# Wolf.net
KiCad netlist of a schematic drawn in EAGLE
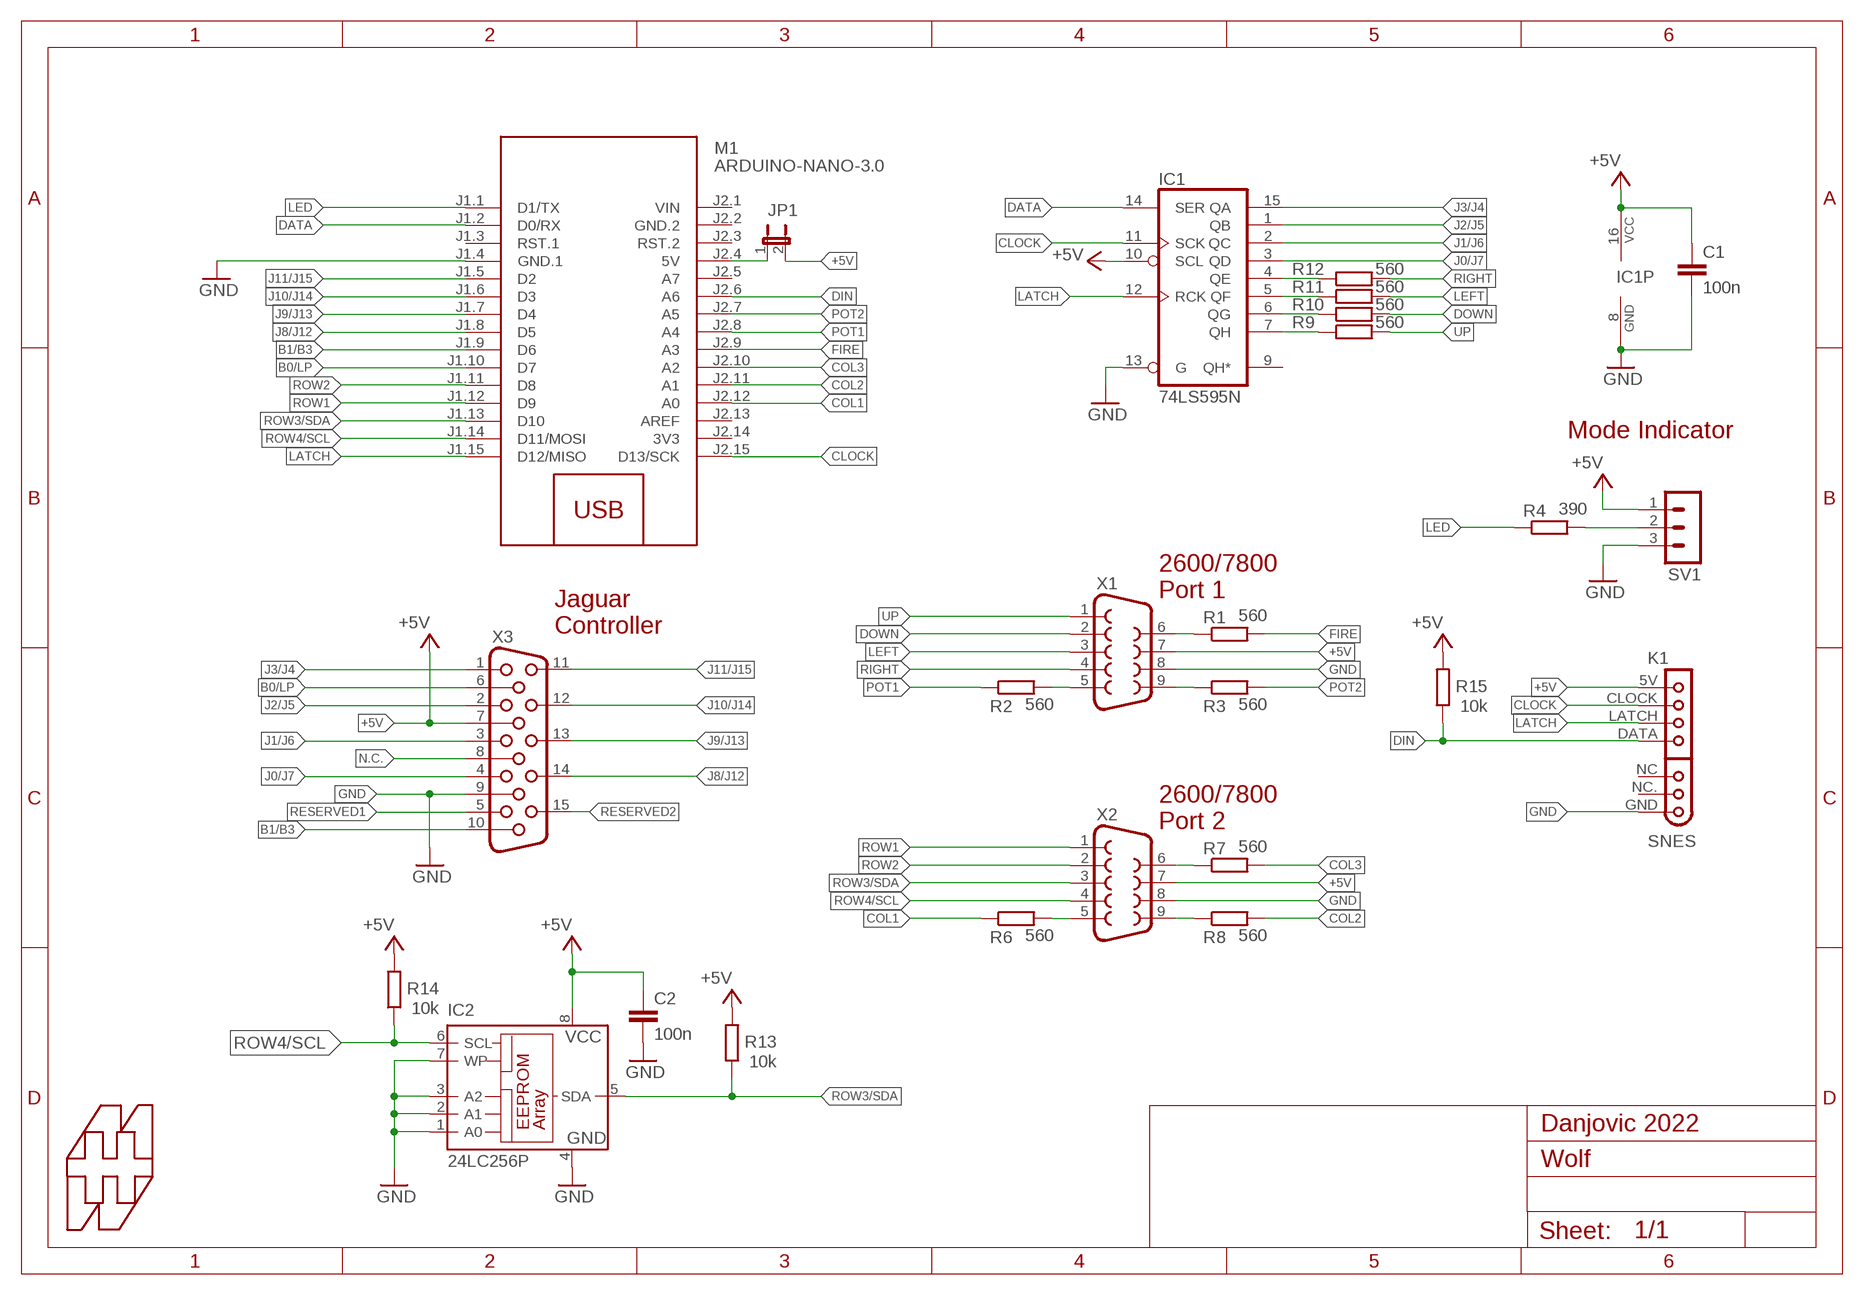
[diagram p0: schematic, sheet 1]

(export (version "E")
  (design (tool "Eeschema 10.0.6"))
  (components
    (comp (ref "C1")
      (value "100n")
      (footprint "eagle-import:C050-024X044")
      (libsource (lib "eagle-import") (part "C-EU050-024X044"))
    )
    (comp (ref "C2")
      (value "100n")
      (footprint "eagle-import:C050-024X044")
      (libsource (lib "eagle-import") (part "C-EU050-024X044"))
    )
    (comp (ref "IC1")
      (value "74LS595N")
      (footprint "eagle-import:DIL16")
      (libsource (lib "eagle-import") (part "74595NLS"))
    )
    (comp (ref "IC2")
      (value "24LC256P")
      (footprint "eagle-import:DIL8")
      (fields (field (name "MF") "MICROCHIP") (field (name "MPN") "24LC256-E/P"))
      (libsource (lib "eagle-import") (part "24PLC256"))
    )
    (comp (ref "JP1")
      (value "JP1E")
      (footprint "eagle-import:JP1")
      (libsource (lib "eagle-import") (part "JP1E"))
    )
    (comp (ref "K1")
      (value "SNES")
      (footprint "eagle-import:SNESCON-R")
      (libsource (lib "eagle-import") (part "SNES-R"))
    )
    (comp (ref "M1")
      (value "ARDUINO-NANO-3.0")
      (footprint "eagle-import:ARDUINO-NANO-3.0")
      (libsource (lib "eagle-import") (part "ARDUINO-NANO-3.0"))
    )
    (comp (ref "R1")
      (value "560")
      (footprint "eagle-import:0204_7")
      (libsource (lib "eagle-import") (part "R-EU_0204/7"))
    )
    (comp (ref "R2")
      (value "560")
      (footprint "eagle-import:0204_7")
      (libsource (lib "eagle-import") (part "R-EU_0204/7"))
    )
    (comp (ref "R3")
      (value "560")
      (footprint "eagle-import:0204_7")
      (libsource (lib "eagle-import") (part "R-EU_0204/7"))
    )
    (comp (ref "R4")
      (value "390")
      (footprint "eagle-import:0204_7")
      (libsource (lib "eagle-import") (part "R-EU_0204/7"))
    )
    (comp (ref "R6")
      (value "560")
      (footprint "eagle-import:0204_7")
      (libsource (lib "eagle-import") (part "R-EU_0204/7"))
    )
    (comp (ref "R7")
      (value "560")
      (footprint "eagle-import:0204_7")
      (libsource (lib "eagle-import") (part "R-EU_0204/7"))
    )
    (comp (ref "R8")
      (value "560")
      (footprint "eagle-import:0204_7")
      (libsource (lib "eagle-import") (part "R-EU_0204/7"))
    )
    (comp (ref "R9")
      (value "560")
      (footprint "eagle-import:0204_7")
      (libsource (lib "eagle-import") (part "R-EU_0204/7"))
    )
    (comp (ref "R10")
      (value "560")
      (footprint "eagle-import:0204_7")
      (libsource (lib "eagle-import") (part "R-EU_0204/7"))
    )
    (comp (ref "R11")
      (value "560")
      (footprint "eagle-import:0204_7")
      (libsource (lib "eagle-import") (part "R-EU_0204/7"))
    )
    (comp (ref "R12")
      (value "560")
      (footprint "eagle-import:0204_7")
      (libsource (lib "eagle-import") (part "R-EU_0204/7"))
    )
    (comp (ref "R13")
      (value "10k")
      (footprint "eagle-import:0204_7")
      (libsource (lib "eagle-import") (part "R-EU_0204/7"))
    )
    (comp (ref "R14")
      (value "10k")
      (footprint "eagle-import:0204_7")
      (libsource (lib "eagle-import") (part "R-EU_0204/7"))
    )
    (comp (ref "R15")
      (value "10k")
      (footprint "eagle-import:0204_7")
      (libsource (lib "eagle-import") (part "R-EU_0204/7"))
    )
    (comp (ref "SV1")
      (value "MA03-1")
      (footprint "eagle-import:MA03-1")
      (libsource (lib "eagle-import") (part "MA03-1"))
    )
    (comp (ref "U$1")
      (value "HAMMOND-RL6015")
      (footprint "eagle-import:RL6015")
      (libsource (lib "eagle-import") (part "HAMMOND-RL6015"))
    )
    (comp (ref "X1")
      (value "F09HP")
      (footprint "eagle-import:F09HP")
      (libsource (lib "eagle-import") (part "F09HP"))
    )
    (comp (ref "X2")
      (value "F09HP")
      (footprint "eagle-import:F09HP")
      (libsource (lib "eagle-import") (part "F09HP"))
    )
    (comp (ref "X3")
      (value "HF15H")
      (footprint "eagle-import:HDF15H")
      (libsource (lib "eagle-import") (part "HF15H"))
    )
  )
  (nets
    (net (code "1") (name "+5V") (class "Default")
      (node (ref "C1") (pin "1") (pinfunction "1_1") (pintype "passive"))
      (node (ref "C2") (pin "1") (pinfunction "1_1") (pintype "passive"))
      (node (ref "IC1") (pin "10") (pinfunction "SCL_10") (pintype "input"))
      (node (ref "IC1") (pin "16") (pinfunction "VCC_16") (pintype "power_in"))
      (node (ref "IC2") (pin "8") (pinfunction "VCC_8") (pintype "power_in"))
      (node (ref "JP1") (pin "2") (pinfunction "2_2") (pintype "passive"))
      (node (ref "K1") (pin "5V") (pinfunction "1_5V") (pintype "passive"))
      (node (ref "R13") (pin "2") (pinfunction "2_2") (pintype "passive"))
      (node (ref "R14") (pin "2") (pinfunction "2_2") (pintype "passive"))
      (node (ref "R15") (pin "2") (pinfunction "2_2") (pintype "passive"))
      (node (ref "SV1") (pin "1") (pinfunction "1_1") (pintype "passive"))
      (node (ref "X1") (pin "7") (pinfunction "7_7") (pintype "passive"))
      (node (ref "X2") (pin "7") (pinfunction "7_7") (pintype "passive"))
      (node (ref "X3") (pin "7") (pinfunction "7_7") (pintype "passive"))
    )
    (net (code "2") (name "/3V3") (class "Default")
      (node (ref "M1") (pin "J2.14") (pinfunction "3V3_J2.14") (pintype "power_in"))
    )
    (net (code "3") (name "/GND.2") (class "Default")
      (node (ref "M1") (pin "J2.2") (pinfunction "GND.2_J2.2") (pintype "power_in"))
    )
    (net (code "4") (name "/VIN") (class "Default")
      (node (ref "M1") (pin "J2.1") (pinfunction "VIN_J2.1") (pintype "power_in"))
    )
    (net (code "5") (name "B0{slash}LP") (class "Default")
      (node (ref "M1") (pin "J1.10") (pinfunction "D7_J1.10") (pintype "bidirectional"))
      (node (ref "X3") (pin "6") (pinfunction "6_6") (pintype "passive"))
    )
    (net (code "6") (name "B1{slash}B3") (class "Default")
      (node (ref "M1") (pin "J1.9") (pinfunction "D6_J1.9") (pintype "bidirectional"))
      (node (ref "X3") (pin "10") (pinfunction "10_10") (pintype "passive"))
    )
    (net (code "7") (name "CLOCK") (class "Default")
      (node (ref "IC1") (pin "11") (pinfunction "SCK_11") (pintype "input"))
      (node (ref "K1") (pin "CLOCK") (pinfunction "2_CLOCK") (pintype "passive"))
      (node (ref "M1") (pin "J2.15") (pinfunction "D13/SCK_J2.15") (pintype "bidirectional"))
    )
    (net (code "8") (name "COL1") (class "Default")
      (node (ref "M1") (pin "J2.12") (pinfunction "A0_J2.12") (pintype "bidirectional"))
      (node (ref "R6") (pin "1") (pinfunction "1_1") (pintype "passive"))
    )
    (net (code "9") (name "COL2") (class "Default")
      (node (ref "M1") (pin "J2.11") (pinfunction "A1_J2.11") (pintype "bidirectional"))
      (node (ref "R8") (pin "2") (pinfunction "2_2") (pintype "passive"))
    )
    (net (code "10") (name "COL3") (class "Default")
      (node (ref "M1") (pin "J2.10") (pinfunction "A2_J2.10") (pintype "bidirectional"))
      (node (ref "R7") (pin "2") (pinfunction "2_2") (pintype "passive"))
    )
    (net (code "11") (name "DATA") (class "Default")
      (node (ref "IC1") (pin "14") (pinfunction "SER_14") (pintype "input"))
      (node (ref "M1") (pin "J1.2") (pinfunction "D0/RX_J1.2") (pintype "bidirectional"))
    )
    (net (code "12") (name "DIN") (class "Default")
      (node (ref "K1") (pin "DATA") (pinfunction "4_DATA") (pintype "passive"))
      (node (ref "M1") (pin "J2.6") (pinfunction "A6_J2.6") (pintype "bidirectional"))
      (node (ref "R15") (pin "1") (pinfunction "1_1") (pintype "passive"))
    )
    (net (code "13") (name "DOWN") (class "Default")
      (node (ref "R10") (pin "2") (pinfunction "2_2") (pintype "passive"))
      (node (ref "X1") (pin "2") (pinfunction "2_2") (pintype "passive"))
    )
    (net (code "14") (name "FIRE") (class "Default")
      (node (ref "M1") (pin "J2.9") (pinfunction "A3_J2.9") (pintype "bidirectional"))
      (node (ref "R1") (pin "2") (pinfunction "2_2") (pintype "passive"))
    )
    (net (code "15") (name "GND") (class "Default")
      (node (ref "C1") (pin "2") (pinfunction "2_2") (pintype "passive"))
      (node (ref "C2") (pin "2") (pinfunction "2_2") (pintype "passive"))
      (node (ref "IC1") (pin "13") (pinfunction "G_13") (pintype "input"))
      (node (ref "IC1") (pin "8") (pinfunction "GND_8") (pintype "power_in"))
      (node (ref "IC2") (pin "1") (pinfunction "A0_1") (pintype "input"))
      (node (ref "IC2") (pin "2") (pinfunction "A1_2") (pintype "input"))
      (node (ref "IC2") (pin "3") (pinfunction "A2_3") (pintype "input"))
      (node (ref "IC2") (pin "4") (pinfunction "GND_4") (pintype "power_in"))
      (node (ref "IC2") (pin "7") (pinfunction "WP_7") (pintype "input"))
      (node (ref "K1") (pin "GND") (pinfunction "7_GND") (pintype "passive"))
      (node (ref "M1") (pin "J1.4") (pinfunction "GND.1_J1.4") (pintype "power_in"))
      (node (ref "SV1") (pin "3") (pinfunction "3_3") (pintype "passive"))
      (node (ref "X1") (pin "8") (pinfunction "8_8") (pintype "passive"))
      (node (ref "X2") (pin "8") (pinfunction "8_8") (pintype "passive"))
      (node (ref "X3") (pin "9") (pinfunction "9_9") (pintype "passive"))
    )
    (net (code "16") (name "J0{slash}J7") (class "Default")
      (node (ref "IC1") (pin "3") (pinfunction "QD_3") (pintype "tri_state"))
      (node (ref "X3") (pin "4") (pinfunction "4_4") (pintype "passive"))
    )
    (net (code "17") (name "J1{slash}J6") (class "Default")
      (node (ref "IC1") (pin "2") (pinfunction "QC_2") (pintype "tri_state"))
      (node (ref "X3") (pin "3") (pinfunction "3_3") (pintype "passive"))
    )
    (net (code "18") (name "J2{slash}J5") (class "Default")
      (node (ref "IC1") (pin "1") (pinfunction "QB_1") (pintype "tri_state"))
      (node (ref "X3") (pin "2") (pinfunction "2_2") (pintype "passive"))
    )
    (net (code "19") (name "J3{slash}J4") (class "Default")
      (node (ref "IC1") (pin "15") (pinfunction "QA_15") (pintype "tri_state"))
      (node (ref "X3") (pin "1") (pinfunction "1_1") (pintype "passive"))
    )
    (net (code "20") (name "J8{slash}J12") (class "Default")
      (node (ref "M1") (pin "J1.8") (pinfunction "D5_J1.8") (pintype "bidirectional"))
      (node (ref "X3") (pin "14") (pinfunction "14_14") (pintype "passive"))
    )
    (net (code "21") (name "J9{slash}J13") (class "Default")
      (node (ref "M1") (pin "J1.7") (pinfunction "D4_J1.7") (pintype "bidirectional"))
      (node (ref "X3") (pin "13") (pinfunction "13_13") (pintype "passive"))
    )
    (net (code "22") (name "J10{slash}J14") (class "Default")
      (node (ref "M1") (pin "J1.6") (pinfunction "D3_J1.6") (pintype "bidirectional"))
      (node (ref "X3") (pin "12") (pinfunction "12_12") (pintype "passive"))
    )
    (net (code "23") (name "J11{slash}J15") (class "Default")
      (node (ref "M1") (pin "J1.5") (pinfunction "D2_J1.5") (pintype "bidirectional"))
      (node (ref "X3") (pin "11") (pinfunction "11_11") (pintype "passive"))
    )
    (net (code "24") (name "LATCH") (class "Default")
      (node (ref "IC1") (pin "12") (pinfunction "RCK_12") (pintype "input"))
      (node (ref "K1") (pin "LATCH") (pinfunction "3_LATCH") (pintype "passive"))
      (node (ref "M1") (pin "J1.15") (pinfunction "D12/MISO_J1.15") (pintype "bidirectional"))
    )
    (net (code "25") (name "LED") (class "Default")
      (node (ref "M1") (pin "J1.1") (pinfunction "D1/TX_J1.1") (pintype "bidirectional"))
      (node (ref "R4") (pin "1") (pinfunction "1_1") (pintype "passive"))
    )
    (net (code "26") (name "LEFT") (class "Default")
      (node (ref "R11") (pin "2") (pinfunction "2_2") (pintype "passive"))
      (node (ref "X1") (pin "3") (pinfunction "3_3") (pintype "passive"))
    )
    (net (code "27") (name "N.C.") (class "Default")
      (node (ref "X3") (pin "8") (pinfunction "8_8") (pintype "passive"))
    )
    (net (code "28") (name "Net-(IC1A-QE)") (class "Default")
      (node (ref "IC1") (pin "4") (pinfunction "QE_4") (pintype "tri_state"))
      (node (ref "R12") (pin "1") (pinfunction "1_1") (pintype "passive"))
    )
    (net (code "29") (name "Net-(IC1A-QF)") (class "Default")
      (node (ref "IC1") (pin "5") (pinfunction "QF_5") (pintype "tri_state"))
      (node (ref "R11") (pin "1") (pinfunction "1_1") (pintype "passive"))
    )
    (net (code "30") (name "Net-(IC1A-QG)") (class "Default")
      (node (ref "IC1") (pin "6") (pinfunction "QG_6") (pintype "tri_state"))
      (node (ref "R10") (pin "1") (pinfunction "1_1") (pintype "passive"))
    )
    (net (code "31") (name "Net-(IC1A-QH)") (class "Default")
      (node (ref "IC1") (pin "7") (pinfunction "QH_7") (pintype "tri_state"))
      (node (ref "R9") (pin "1") (pinfunction "1_1") (pintype "passive"))
    )
    (net (code "32") (name "Net-(M1-5V)") (class "Default")
      (node (ref "JP1") (pin "1") (pinfunction "1_1") (pintype "passive"))
      (node (ref "M1") (pin "J2.4") (pinfunction "5V_J2.4") (pintype "power_in"))
    )
    (net (code "33") (name "Net-(R1-Pad1)") (class "Default")
      (node (ref "R1") (pin "1") (pinfunction "1_1") (pintype "passive"))
      (node (ref "X1") (pin "6") (pinfunction "6_6") (pintype "passive"))
    )
    (net (code "34") (name "Net-(R2-Pad2)") (class "Default")
      (node (ref "R2") (pin "2") (pinfunction "2_2") (pintype "passive"))
      (node (ref "X1") (pin "5") (pinfunction "5_5") (pintype "passive"))
    )
    (net (code "35") (name "Net-(R3-Pad1)") (class "Default")
      (node (ref "R3") (pin "1") (pinfunction "1_1") (pintype "passive"))
      (node (ref "X1") (pin "9") (pinfunction "9_9") (pintype "passive"))
    )
    (net (code "36") (name "Net-(R4-Pad2)") (class "Default")
      (node (ref "R4") (pin "2") (pinfunction "2_2") (pintype "passive"))
      (node (ref "SV1") (pin "2") (pinfunction "2_2") (pintype "passive"))
    )
    (net (code "37") (name "Net-(R6-Pad2)") (class "Default")
      (node (ref "R6") (pin "2") (pinfunction "2_2") (pintype "passive"))
      (node (ref "X2") (pin "5") (pinfunction "5_5") (pintype "passive"))
    )
    (net (code "38") (name "Net-(R7-Pad1)") (class "Default")
      (node (ref "R7") (pin "1") (pinfunction "1_1") (pintype "passive"))
      (node (ref "X2") (pin "6") (pinfunction "6_6") (pintype "passive"))
    )
    (net (code "39") (name "Net-(R8-Pad1)") (class "Default")
      (node (ref "R8") (pin "1") (pinfunction "1_1") (pintype "passive"))
      (node (ref "X2") (pin "9") (pinfunction "9_9") (pintype "passive"))
    )
    (net (code "40") (name "POT1") (class "Default")
      (node (ref "M1") (pin "J2.8") (pinfunction "A4_J2.8") (pintype "bidirectional"))
      (node (ref "R2") (pin "1") (pinfunction "1_1") (pintype "passive"))
    )
    (net (code "41") (name "POT2") (class "Default")
      (node (ref "M1") (pin "J2.7") (pinfunction "A5_J2.7") (pintype "bidirectional"))
      (node (ref "R3") (pin "2") (pinfunction "2_2") (pintype "passive"))
    )
    (net (code "42") (name "RESERVED1") (class "Default")
      (node (ref "X3") (pin "5") (pinfunction "5_5") (pintype "passive"))
    )
    (net (code "43") (name "RESERVED2") (class "Default")
      (node (ref "X3") (pin "15") (pinfunction "15_15") (pintype "passive"))
    )
    (net (code "44") (name "RIGHT") (class "Default")
      (node (ref "R12") (pin "2") (pinfunction "2_2") (pintype "passive"))
      (node (ref "X1") (pin "4") (pinfunction "4_4") (pintype "passive"))
    )
    (net (code "45") (name "ROW1") (class "Default")
      (node (ref "M1") (pin "J1.12") (pinfunction "D9_J1.12") (pintype "bidirectional"))
      (node (ref "X2") (pin "1") (pinfunction "1_1") (pintype "passive"))
    )
    (net (code "46") (name "ROW2") (class "Default")
      (node (ref "M1") (pin "J1.11") (pinfunction "D8_J1.11") (pintype "bidirectional"))
      (node (ref "X2") (pin "2") (pinfunction "2_2") (pintype "passive"))
    )
    (net (code "47") (name "ROW3{slash}SDA") (class "Default")
      (node (ref "IC2") (pin "5") (pinfunction "SDA_5") (pintype "bidirectional"))
      (node (ref "M1") (pin "J1.13") (pinfunction "D10_J1.13") (pintype "bidirectional"))
      (node (ref "R13") (pin "1") (pinfunction "1_1") (pintype "passive"))
      (node (ref "X2") (pin "3") (pinfunction "3_3") (pintype "passive"))
    )
    (net (code "48") (name "ROW4{slash}SCL") (class "Default")
      (node (ref "IC2") (pin "6") (pinfunction "SCL_6") (pintype "input"))
      (node (ref "M1") (pin "J1.14") (pinfunction "D11/MOSI_J1.14") (pintype "bidirectional"))
      (node (ref "R14") (pin "1") (pinfunction "1_1") (pintype "passive"))
      (node (ref "X2") (pin "4") (pinfunction "4_4") (pintype "passive"))
    )
    (net (code "49") (name "UP") (class "Default")
      (node (ref "R9") (pin "2") (pinfunction "2_2") (pintype "passive"))
      (node (ref "X1") (pin "1") (pinfunction "1_1") (pintype "passive"))
    )
    (net (code "50") (name "unconnected-(IC1A-QH*-Pad9)") (class "Default")
      (node (ref "IC1") (pin "9") (pinfunction "QH*_9") (pintype "tri_state"))
    )
    (net (code "51") (name "unconnected-(K1-5-PadNC)") (class "Default")
      (node (ref "K1") (pin "NC") (pinfunction "5_NC") (pintype "passive"))
    )
    (net (code "52") (name "unconnected-(K1-6-PadNC.)") (class "Default")
      (node (ref "K1") (pin "NC.") (pinfunction "6_NC.") (pintype "passive"))
    )
    (net (code "53") (name "unconnected-(M1-A7-PadJ2.5)") (class "Default")
      (node (ref "M1") (pin "J2.5") (pinfunction "A7_J2.5") (pintype "bidirectional"))
    )
    (net (code "54") (name "unconnected-(M1-AREF-PadJ2.13)") (class "Default")
      (node (ref "M1") (pin "J2.13") (pinfunction "AREF_J2.13") (pintype "bidirectional"))
    )
    (net (code "55") (name "unconnected-(M1-RST.1-PadJ1.3)") (class "Default")
      (node (ref "M1") (pin "J1.3") (pinfunction "RST.1_J1.3") (pintype "bidirectional"))
    )
    (net (code "56") (name "unconnected-(M1-RST.2-PadJ2.3)") (class "Default")
      (node (ref "M1") (pin "J2.3") (pinfunction "RST.2_J2.3") (pintype "bidirectional"))
    )
  )
)
